# potenciostato_last.net
KiCad netlist of a schematic drawn in EAGLE
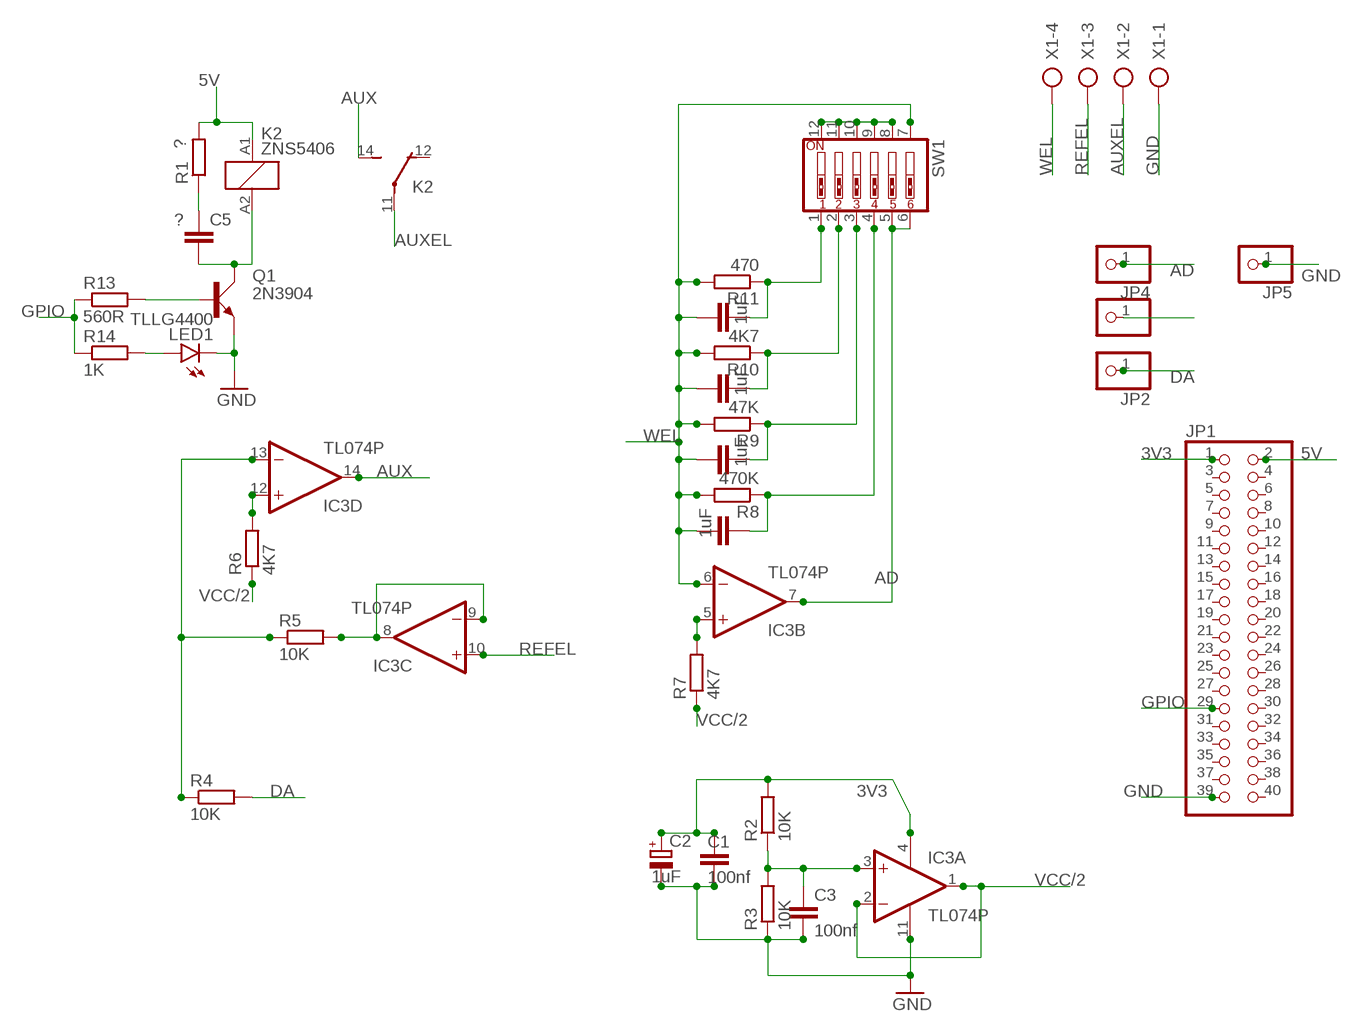
[diagram p0: schematic, sheet 1]

(export (version "E")
  (design (tool "Eeschema 10.0.6"))
  (components
    (comp (ref "C1")
      (value "100nf")
      (footprint "eagle-import:C050-035X075")
      (libsource (lib "eagle-import") (part "C-EU050-035X075"))
    )
    (comp (ref "C2")
      (value "1uF")
      (footprint "eagle-import:E2,5-5")
      (libsource (lib "eagle-import") (part "CPOL-EUE2.5-5"))
    )
    (comp (ref "C3")
      (value "100nf")
      (footprint "eagle-import:C050-035X075")
      (libsource (lib "eagle-import") (part "C-EU050-035X075"))
    )
    (comp (ref "C4")
      (value "1uF")
      (footprint "eagle-import:C050-035X075")
      (libsource (lib "eagle-import") (part "C-EU050-035X075"))
    )
    (comp (ref "C5")
      (value "?")
      (footprint "eagle-import:C050-035X075")
      (libsource (lib "eagle-import") (part "C-EU050-035X075"))
    )
    (comp (ref "C6")
      (value "1uF")
      (footprint "eagle-import:C050-035X075")
      (libsource (lib "eagle-import") (part "C-EU050-035X075"))
    )
    (comp (ref "C7")
      (value "1uF")
      (footprint "eagle-import:C050-035X075")
      (libsource (lib "eagle-import") (part "C-EU050-035X075"))
    )
    (comp (ref "C8")
      (value "1uF")
      (footprint "eagle-import:C050-035X075")
      (libsource (lib "eagle-import") (part "C-EU050-035X075"))
    )
    (comp (ref "IC3")
      (value "TL074P")
      (footprint "eagle-import:DIL14")
      (libsource (lib "eagle-import") (part "TL074P"))
    )
    (comp (ref "JP1")
      (value "PINHD-2X20/90")
      (footprint "eagle-import:2X20_90")
      (libsource (lib "eagle-import") (part "PINHD-2X20/90"))
    )
    (comp (ref "JP2")
      (value "PINHD-1X1")
      (footprint "eagle-import:1X01")
      (libsource (lib "eagle-import") (part "PINHD-1X1"))
    )
    (comp (ref "JP3")
      (value "PINHD-1X1")
      (footprint "eagle-import:1X01")
      (libsource (lib "eagle-import") (part "PINHD-1X1"))
    )
    (comp (ref "JP4")
      (value "PINHD-1X1")
      (footprint "eagle-import:1X01")
      (libsource (lib "eagle-import") (part "PINHD-1X1"))
    )
    (comp (ref "JP5")
      (value "PINHD-1X1")
      (footprint "eagle-import:1X01")
      (libsource (lib "eagle-import") (part "PINHD-1X1"))
    )
    (comp (ref "K2")
      (value "ZNS5406")
      (footprint "eagle-import:ZN5")
      (libsource (lib "eagle-import") (part "ZNS5406"))
    )
    (comp (ref "LED1")
      (value "TLLG4400")
      (footprint "eagle-import:LED3MM")
      (fields (field (name "MF") "VISHAY SEMICONDUCTOR"))
      (libsource (lib "eagle-import") (part "TLLG4400"))
    )
    (comp (ref "Q1")
      (value "2N3904")
      (footprint "eagle-import:TO92D")
      (libsource (lib "eagle-import") (part "2N3904"))
    )
    (comp (ref "R1")
      (value "?")
      (footprint "eagle-import:0207_7")
      (libsource (lib "eagle-import") (part "R-EU_0207/7"))
    )
    (comp (ref "R2")
      (value "10K")
      (footprint "eagle-import:0207_7")
      (libsource (lib "eagle-import") (part "R-EU_0207/7"))
    )
    (comp (ref "R3")
      (value "10K")
      (footprint "eagle-import:0207_7")
      (libsource (lib "eagle-import") (part "R-EU_0207/7"))
    )
    (comp (ref "R4")
      (value "10K")
      (footprint "eagle-import:0207_7")
      (libsource (lib "eagle-import") (part "R-EU_0207/7"))
    )
    (comp (ref "R5")
      (value "10K")
      (footprint "eagle-import:0207_7")
      (libsource (lib "eagle-import") (part "R-EU_0207/7"))
    )
    (comp (ref "R6")
      (value "4K7")
      (footprint "eagle-import:0207_7")
      (libsource (lib "eagle-import") (part "R-EU_0207/7"))
    )
    (comp (ref "R7")
      (value "4K7")
      (footprint "eagle-import:0207_7")
      (libsource (lib "eagle-import") (part "R-EU_0207/7"))
    )
    (comp (ref "R8")
      (value "470K")
      (footprint "eagle-import:0207_7")
      (libsource (lib "eagle-import") (part "R-EU_0207/7"))
    )
    (comp (ref "R9")
      (value "47K")
      (footprint "eagle-import:0207_7")
      (libsource (lib "eagle-import") (part "R-EU_0207/7"))
    )
    (comp (ref "R10")
      (value "4K7")
      (footprint "eagle-import:0207_7")
      (libsource (lib "eagle-import") (part "R-EU_0207/7"))
    )
    (comp (ref "R11")
      (value "470")
      (footprint "eagle-import:0207_7")
      (libsource (lib "eagle-import") (part "R-EU_0207/7"))
    )
    (comp (ref "R13")
      (value "560R")
      (footprint "eagle-import:0207_7")
      (libsource (lib "eagle-import") (part "R-EU_0207/7"))
    )
    (comp (ref "R14")
      (value "1K")
      (footprint "eagle-import:0207_7")
      (libsource (lib "eagle-import") (part "R-EU_0207/7"))
    )
    (comp (ref "SW1")
      (value "SW_DIP-6")
      (footprint "eagle-import:EDG-06")
      (libsource (lib "eagle-import") (part "SW_DIP-6"))
    )
    (comp (ref "X1")
      (value "AK500/4")
      (footprint "eagle-import:AK500_4")
      (libsource (lib "eagle-import") (part "AK500/4"))
    )
  )
  (nets
    (net (code "1") (name "/3V3") (class "Default")
      (node (ref "C1") (pin "1") (pinfunction "1_1") (pintype "passive"))
      (node (ref "C2") (pin "+") (pinfunction "+_+") (pintype "passive"))
      (node (ref "IC3") (pin "4") (pinfunction "V+_4") (pintype "power_in"))
      (node (ref "JP1") (pin "1") (pinfunction "1_1") (pintype "passive"))
      (node (ref "R2") (pin "2") (pinfunction "2_2") (pintype "passive"))
    )
    (net (code "2") (name "/5V") (class "Default")
      (node (ref "JP1") (pin "2") (pinfunction "2_2") (pintype "passive"))
      (node (ref "K2") (pin "A1") (pinfunction "1_A1") (pintype "passive"))
      (node (ref "R1") (pin "2") (pinfunction "2_2") (pintype "passive"))
    )
    (net (code "3") (name "/AD") (class "Default")
      (node (ref "IC3") (pin "7") (pinfunction "OUT_7") (pintype "output"))
      (node (ref "JP4") (pin "1") (pinfunction "1_1") (pintype "passive"))
      (node (ref "SW1") (pin "5") (pinfunction "5_5") (pintype "passive"))
      (node (ref "SW1") (pin "6") (pinfunction "6_6") (pintype "passive"))
    )
    (net (code "4") (name "/AUX") (class "Default")
      (node (ref "IC3") (pin "14") (pinfunction "OUT_14") (pintype "output"))
      (node (ref "K2") (pin "14") (pinfunction "S_14") (pintype "passive"))
    )
    (net (code "5") (name "/AUXEL") (class "Default")
      (node (ref "K2") (pin "11") (pinfunction "P_11") (pintype "passive"))
      (node (ref "X1") (pin "2") (pinfunction "KL_2") (pintype "passive"))
    )
    (net (code "6") (name "/DA") (class "Default")
      (node (ref "JP2") (pin "1") (pinfunction "1_1") (pintype "passive"))
      (node (ref "R4") (pin "2") (pinfunction "2_2") (pintype "passive"))
    )
    (net (code "7") (name "/GPIO") (class "Default")
      (node (ref "JP1") (pin "29") (pinfunction "29_29") (pintype "passive"))
      (node (ref "R13") (pin "1") (pinfunction "1_1") (pintype "passive"))
      (node (ref "R14") (pin "1") (pinfunction "1_1") (pintype "passive"))
    )
    (net (code "8") (name "/REFEL") (class "Default")
      (node (ref "IC3") (pin "10") (pinfunction "+IN_10") (pintype "input"))
      (node (ref "X1") (pin "3") (pinfunction "KL_3") (pintype "passive"))
    )
    (net (code "9") (name "/VCC{slash}2") (class "Default")
      (node (ref "IC3") (pin "1") (pinfunction "OUT_1") (pintype "output"))
      (node (ref "IC3") (pin "2") (pinfunction "-IN_2") (pintype "input"))
      (node (ref "R6") (pin "1") (pinfunction "1_1") (pintype "passive"))
      (node (ref "R7") (pin "1") (pinfunction "1_1") (pintype "passive"))
    )
    (net (code "10") (name "/WEL") (class "Default")
      (node (ref "C4") (pin "1") (pinfunction "1_1") (pintype "passive"))
      (node (ref "C6") (pin "1") (pinfunction "1_1") (pintype "passive"))
      (node (ref "C7") (pin "1") (pinfunction "1_1") (pintype "passive"))
      (node (ref "C8") (pin "1") (pinfunction "1_1") (pintype "passive"))
      (node (ref "IC3") (pin "6") (pinfunction "-IN_6") (pintype "input"))
      (node (ref "R10") (pin "2") (pinfunction "2_2") (pintype "passive"))
      (node (ref "R11") (pin "2") (pinfunction "2_2") (pintype "passive"))
      (node (ref "R8") (pin "2") (pinfunction "2_2") (pintype "passive"))
      (node (ref "R9") (pin "2") (pinfunction "2_2") (pintype "passive"))
      (node (ref "SW1") (pin "7") (pinfunction "7_7") (pintype "passive"))
      (node (ref "X1") (pin "4") (pinfunction "KL_4") (pintype "passive"))
    )
    (net (code "11") (name "GND") (class "Default")
      (node (ref "C1") (pin "2") (pinfunction "2_2") (pintype "passive"))
      (node (ref "C2") (pin "-") (pinfunction "-_-") (pintype "passive"))
      (node (ref "C3") (pin "2") (pinfunction "2_2") (pintype "passive"))
      (node (ref "IC3") (pin "11") (pinfunction "V-_11") (pintype "power_in"))
      (node (ref "JP1") (pin "39") (pinfunction "39_39") (pintype "passive"))
      (node (ref "JP5") (pin "1") (pinfunction "1_1") (pintype "passive"))
      (node (ref "LED1") (pin "K") (pinfunction "C_K") (pintype "passive"))
      (node (ref "Q1") (pin "E") (pinfunction "E_E") (pintype "passive"))
      (node (ref "R3") (pin "1") (pinfunction "1_1") (pintype "passive"))
      (node (ref "X1") (pin "1") (pinfunction "KL_1") (pintype "passive"))
    )
    (net (code "12") (name "Net-(C4-Pad2)") (class "Default")
      (node (ref "C4") (pin "2") (pinfunction "2_2") (pintype "passive"))
      (node (ref "R8") (pin "1") (pinfunction "1_1") (pintype "passive"))
      (node (ref "SW1") (pin "4") (pinfunction "4_4") (pintype "passive"))
    )
    (net (code "13") (name "Net-(C5-Pad1)") (class "Default")
      (node (ref "C5") (pin "1") (pinfunction "1_1") (pintype "passive"))
      (node (ref "R1") (pin "1") (pinfunction "1_1") (pintype "passive"))
    )
    (net (code "14") (name "Net-(C6-Pad2)") (class "Default")
      (node (ref "C6") (pin "2") (pinfunction "2_2") (pintype "passive"))
      (node (ref "R11") (pin "1") (pinfunction "1_1") (pintype "passive"))
      (node (ref "SW1") (pin "1") (pinfunction "1_1") (pintype "passive"))
    )
    (net (code "15") (name "Net-(C7-Pad2)") (class "Default")
      (node (ref "C7") (pin "2") (pinfunction "2_2") (pintype "passive"))
      (node (ref "R10") (pin "1") (pinfunction "1_1") (pintype "passive"))
      (node (ref "SW1") (pin "2") (pinfunction "2_2") (pintype "passive"))
    )
    (net (code "16") (name "Net-(C8-Pad2)") (class "Default")
      (node (ref "C8") (pin "2") (pinfunction "2_2") (pintype "passive"))
      (node (ref "R9") (pin "1") (pinfunction "1_1") (pintype "passive"))
      (node (ref "SW1") (pin "3") (pinfunction "3_3") (pintype "passive"))
    )
    (net (code "17") (name "Net-(IC3A-+IN)") (class "Default")
      (node (ref "C3") (pin "1") (pinfunction "1_1") (pintype "passive"))
      (node (ref "IC3") (pin "3") (pinfunction "+IN_3") (pintype "input"))
      (node (ref "R2") (pin "1") (pinfunction "1_1") (pintype "passive"))
      (node (ref "R3") (pin "2") (pinfunction "2_2") (pintype "passive"))
    )
    (net (code "18") (name "Net-(IC3B-+IN)") (class "Default")
      (node (ref "IC3") (pin "5") (pinfunction "+IN_5") (pintype "input"))
      (node (ref "R7") (pin "2") (pinfunction "2_2") (pintype "passive"))
    )
    (net (code "19") (name "Net-(IC3C--IN)") (class "Default")
      (node (ref "IC3") (pin "8") (pinfunction "OUT_8") (pintype "output"))
      (node (ref "IC3") (pin "9") (pinfunction "-IN_9") (pintype "input"))
      (node (ref "R5") (pin "2") (pinfunction "2_2") (pintype "passive"))
    )
    (net (code "20") (name "Net-(IC3D-+IN)") (class "Default")
      (node (ref "IC3") (pin "12") (pinfunction "+IN_12") (pintype "input"))
      (node (ref "R6") (pin "2") (pinfunction "2_2") (pintype "passive"))
    )
    (net (code "21") (name "Net-(IC3D--IN)") (class "Default")
      (node (ref "IC3") (pin "13") (pinfunction "-IN_13") (pintype "input"))
      (node (ref "R4") (pin "1") (pinfunction "1_1") (pintype "passive"))
      (node (ref "R5") (pin "1") (pinfunction "1_1") (pintype "passive"))
    )
    (net (code "22") (name "Net-(K2A-2)") (class "Default")
      (node (ref "C5") (pin "2") (pinfunction "2_2") (pintype "passive"))
      (node (ref "K2") (pin "A2") (pinfunction "2_A2") (pintype "passive"))
      (node (ref "Q1") (pin "C") (pinfunction "C_C") (pintype "passive"))
    )
    (net (code "23") (name "Net-(LED1-PadA)") (class "Default")
      (node (ref "LED1") (pin "A") (pinfunction "A_A") (pintype "passive"))
      (node (ref "R14") (pin "2") (pinfunction "2_2") (pintype "passive"))
    )
    (net (code "24") (name "Net-(Q1-PadB)") (class "Default")
      (node (ref "Q1") (pin "B") (pinfunction "B_B") (pintype "passive"))
      (node (ref "R13") (pin "2") (pinfunction "2_2") (pintype "passive"))
    )
    (net (code "25") (name "Net-(SW1-Pad10)") (class "Default")
      (node (ref "SW1") (pin "10") (pinfunction "10_10") (pintype "passive"))
      (node (ref "SW1") (pin "11") (pinfunction "11_11") (pintype "passive"))
      (node (ref "SW1") (pin "12") (pinfunction "12_12") (pintype "passive"))
      (node (ref "SW1") (pin "8") (pinfunction "8_8") (pintype "passive"))
      (node (ref "SW1") (pin "9") (pinfunction "9_9") (pintype "passive"))
    )
    (net (code "26") (name "unconnected-(JP1-Pad3)") (class "Default")
      (node (ref "JP1") (pin "3") (pinfunction "3_3") (pintype "passive"))
    )
    (net (code "27") (name "unconnected-(JP1-Pad4)") (class "Default")
      (node (ref "JP1") (pin "4") (pinfunction "4_4") (pintype "passive"))
    )
    (net (code "28") (name "unconnected-(JP1-Pad5)") (class "Default")
      (node (ref "JP1") (pin "5") (pinfunction "5_5") (pintype "passive"))
    )
    (net (code "29") (name "unconnected-(JP1-Pad6)") (class "Default")
      (node (ref "JP1") (pin "6") (pinfunction "6_6") (pintype "passive"))
    )
    (net (code "30") (name "unconnected-(JP1-Pad7)") (class "Default")
      (node (ref "JP1") (pin "7") (pinfunction "7_7") (pintype "passive"))
    )
    (net (code "31") (name "unconnected-(JP1-Pad8)") (class "Default")
      (node (ref "JP1") (pin "8") (pinfunction "8_8") (pintype "passive"))
    )
    (net (code "32") (name "unconnected-(JP1-Pad9)") (class "Default")
      (node (ref "JP1") (pin "9") (pinfunction "9_9") (pintype "passive"))
    )
    (net (code "33") (name "unconnected-(JP1-Pad10)") (class "Default")
      (node (ref "JP1") (pin "10") (pinfunction "10_10") (pintype "passive"))
    )
    (net (code "34") (name "unconnected-(JP1-Pad11)") (class "Default")
      (node (ref "JP1") (pin "11") (pinfunction "11_11") (pintype "passive"))
    )
    (net (code "35") (name "unconnected-(JP1-Pad12)") (class "Default")
      (node (ref "JP1") (pin "12") (pinfunction "12_12") (pintype "passive"))
    )
    (net (code "36") (name "unconnected-(JP1-Pad13)") (class "Default")
      (node (ref "JP1") (pin "13") (pinfunction "13_13") (pintype "passive"))
    )
    (net (code "37") (name "unconnected-(JP1-Pad14)") (class "Default")
      (node (ref "JP1") (pin "14") (pinfunction "14_14") (pintype "passive"))
    )
    (net (code "38") (name "unconnected-(JP1-Pad15)") (class "Default")
      (node (ref "JP1") (pin "15") (pinfunction "15_15") (pintype "passive"))
    )
    (net (code "39") (name "unconnected-(JP1-Pad16)") (class "Default")
      (node (ref "JP1") (pin "16") (pinfunction "16_16") (pintype "passive"))
    )
    (net (code "40") (name "unconnected-(JP1-Pad17)") (class "Default")
      (node (ref "JP1") (pin "17") (pinfunction "17_17") (pintype "passive"))
    )
    (net (code "41") (name "unconnected-(JP1-Pad18)") (class "Default")
      (node (ref "JP1") (pin "18") (pinfunction "18_18") (pintype "passive"))
    )
    (net (code "42") (name "unconnected-(JP1-Pad19)") (class "Default")
      (node (ref "JP1") (pin "19") (pinfunction "19_19") (pintype "passive"))
    )
    (net (code "43") (name "unconnected-(JP1-Pad20)") (class "Default")
      (node (ref "JP1") (pin "20") (pinfunction "20_20") (pintype "passive"))
    )
    (net (code "44") (name "unconnected-(JP1-Pad21)") (class "Default")
      (node (ref "JP1") (pin "21") (pinfunction "21_21") (pintype "passive"))
    )
    (net (code "45") (name "unconnected-(JP1-Pad22)") (class "Default")
      (node (ref "JP1") (pin "22") (pinfunction "22_22") (pintype "passive"))
    )
    (net (code "46") (name "unconnected-(JP1-Pad23)") (class "Default")
      (node (ref "JP1") (pin "23") (pinfunction "23_23") (pintype "passive"))
    )
    (net (code "47") (name "unconnected-(JP1-Pad24)") (class "Default")
      (node (ref "JP1") (pin "24") (pinfunction "24_24") (pintype "passive"))
    )
    (net (code "48") (name "unconnected-(JP1-Pad25)") (class "Default")
      (node (ref "JP1") (pin "25") (pinfunction "25_25") (pintype "passive"))
    )
    (net (code "49") (name "unconnected-(JP1-Pad26)") (class "Default")
      (node (ref "JP1") (pin "26") (pinfunction "26_26") (pintype "passive"))
    )
    (net (code "50") (name "unconnected-(JP1-Pad27)") (class "Default")
      (node (ref "JP1") (pin "27") (pinfunction "27_27") (pintype "passive"))
    )
    (net (code "51") (name "unconnected-(JP1-Pad28)") (class "Default")
      (node (ref "JP1") (pin "28") (pinfunction "28_28") (pintype "passive"))
    )
    (net (code "52") (name "unconnected-(JP1-Pad30)") (class "Default")
      (node (ref "JP1") (pin "30") (pinfunction "30_30") (pintype "passive"))
    )
    (net (code "53") (name "unconnected-(JP1-Pad31)") (class "Default")
      (node (ref "JP1") (pin "31") (pinfunction "31_31") (pintype "passive"))
    )
    (net (code "54") (name "unconnected-(JP1-Pad32)") (class "Default")
      (node (ref "JP1") (pin "32") (pinfunction "32_32") (pintype "passive"))
    )
    (net (code "55") (name "unconnected-(JP1-Pad33)") (class "Default")
      (node (ref "JP1") (pin "33") (pinfunction "33_33") (pintype "passive"))
    )
    (net (code "56") (name "unconnected-(JP1-Pad34)") (class "Default")
      (node (ref "JP1") (pin "34") (pinfunction "34_34") (pintype "passive"))
    )
    (net (code "57") (name "unconnected-(JP1-Pad35)") (class "Default")
      (node (ref "JP1") (pin "35") (pinfunction "35_35") (pintype "passive"))
    )
    (net (code "58") (name "unconnected-(JP1-Pad36)") (class "Default")
      (node (ref "JP1") (pin "36") (pinfunction "36_36") (pintype "passive"))
    )
    (net (code "59") (name "unconnected-(JP1-Pad37)") (class "Default")
      (node (ref "JP1") (pin "37") (pinfunction "37_37") (pintype "passive"))
    )
    (net (code "60") (name "unconnected-(JP1-Pad38)") (class "Default")
      (node (ref "JP1") (pin "38") (pinfunction "38_38") (pintype "passive"))
    )
    (net (code "61") (name "unconnected-(JP1-Pad40)") (class "Default")
      (node (ref "JP1") (pin "40") (pinfunction "40_40") (pintype "passive"))
    )
    (net (code "62") (name "unconnected-(JP3-Pad1)") (class "Default")
      (node (ref "JP3") (pin "1") (pinfunction "1_1") (pintype "passive"))
    )
    (net (code "63") (name "unconnected-(K2B-O-Pad12)") (class "Default")
      (node (ref "K2") (pin "12") (pinfunction "O_12") (pintype "passive"))
    )
  )
)
